# 601_GridPos6.net
KiCad netlist of a schematic drawn in Altium Designer
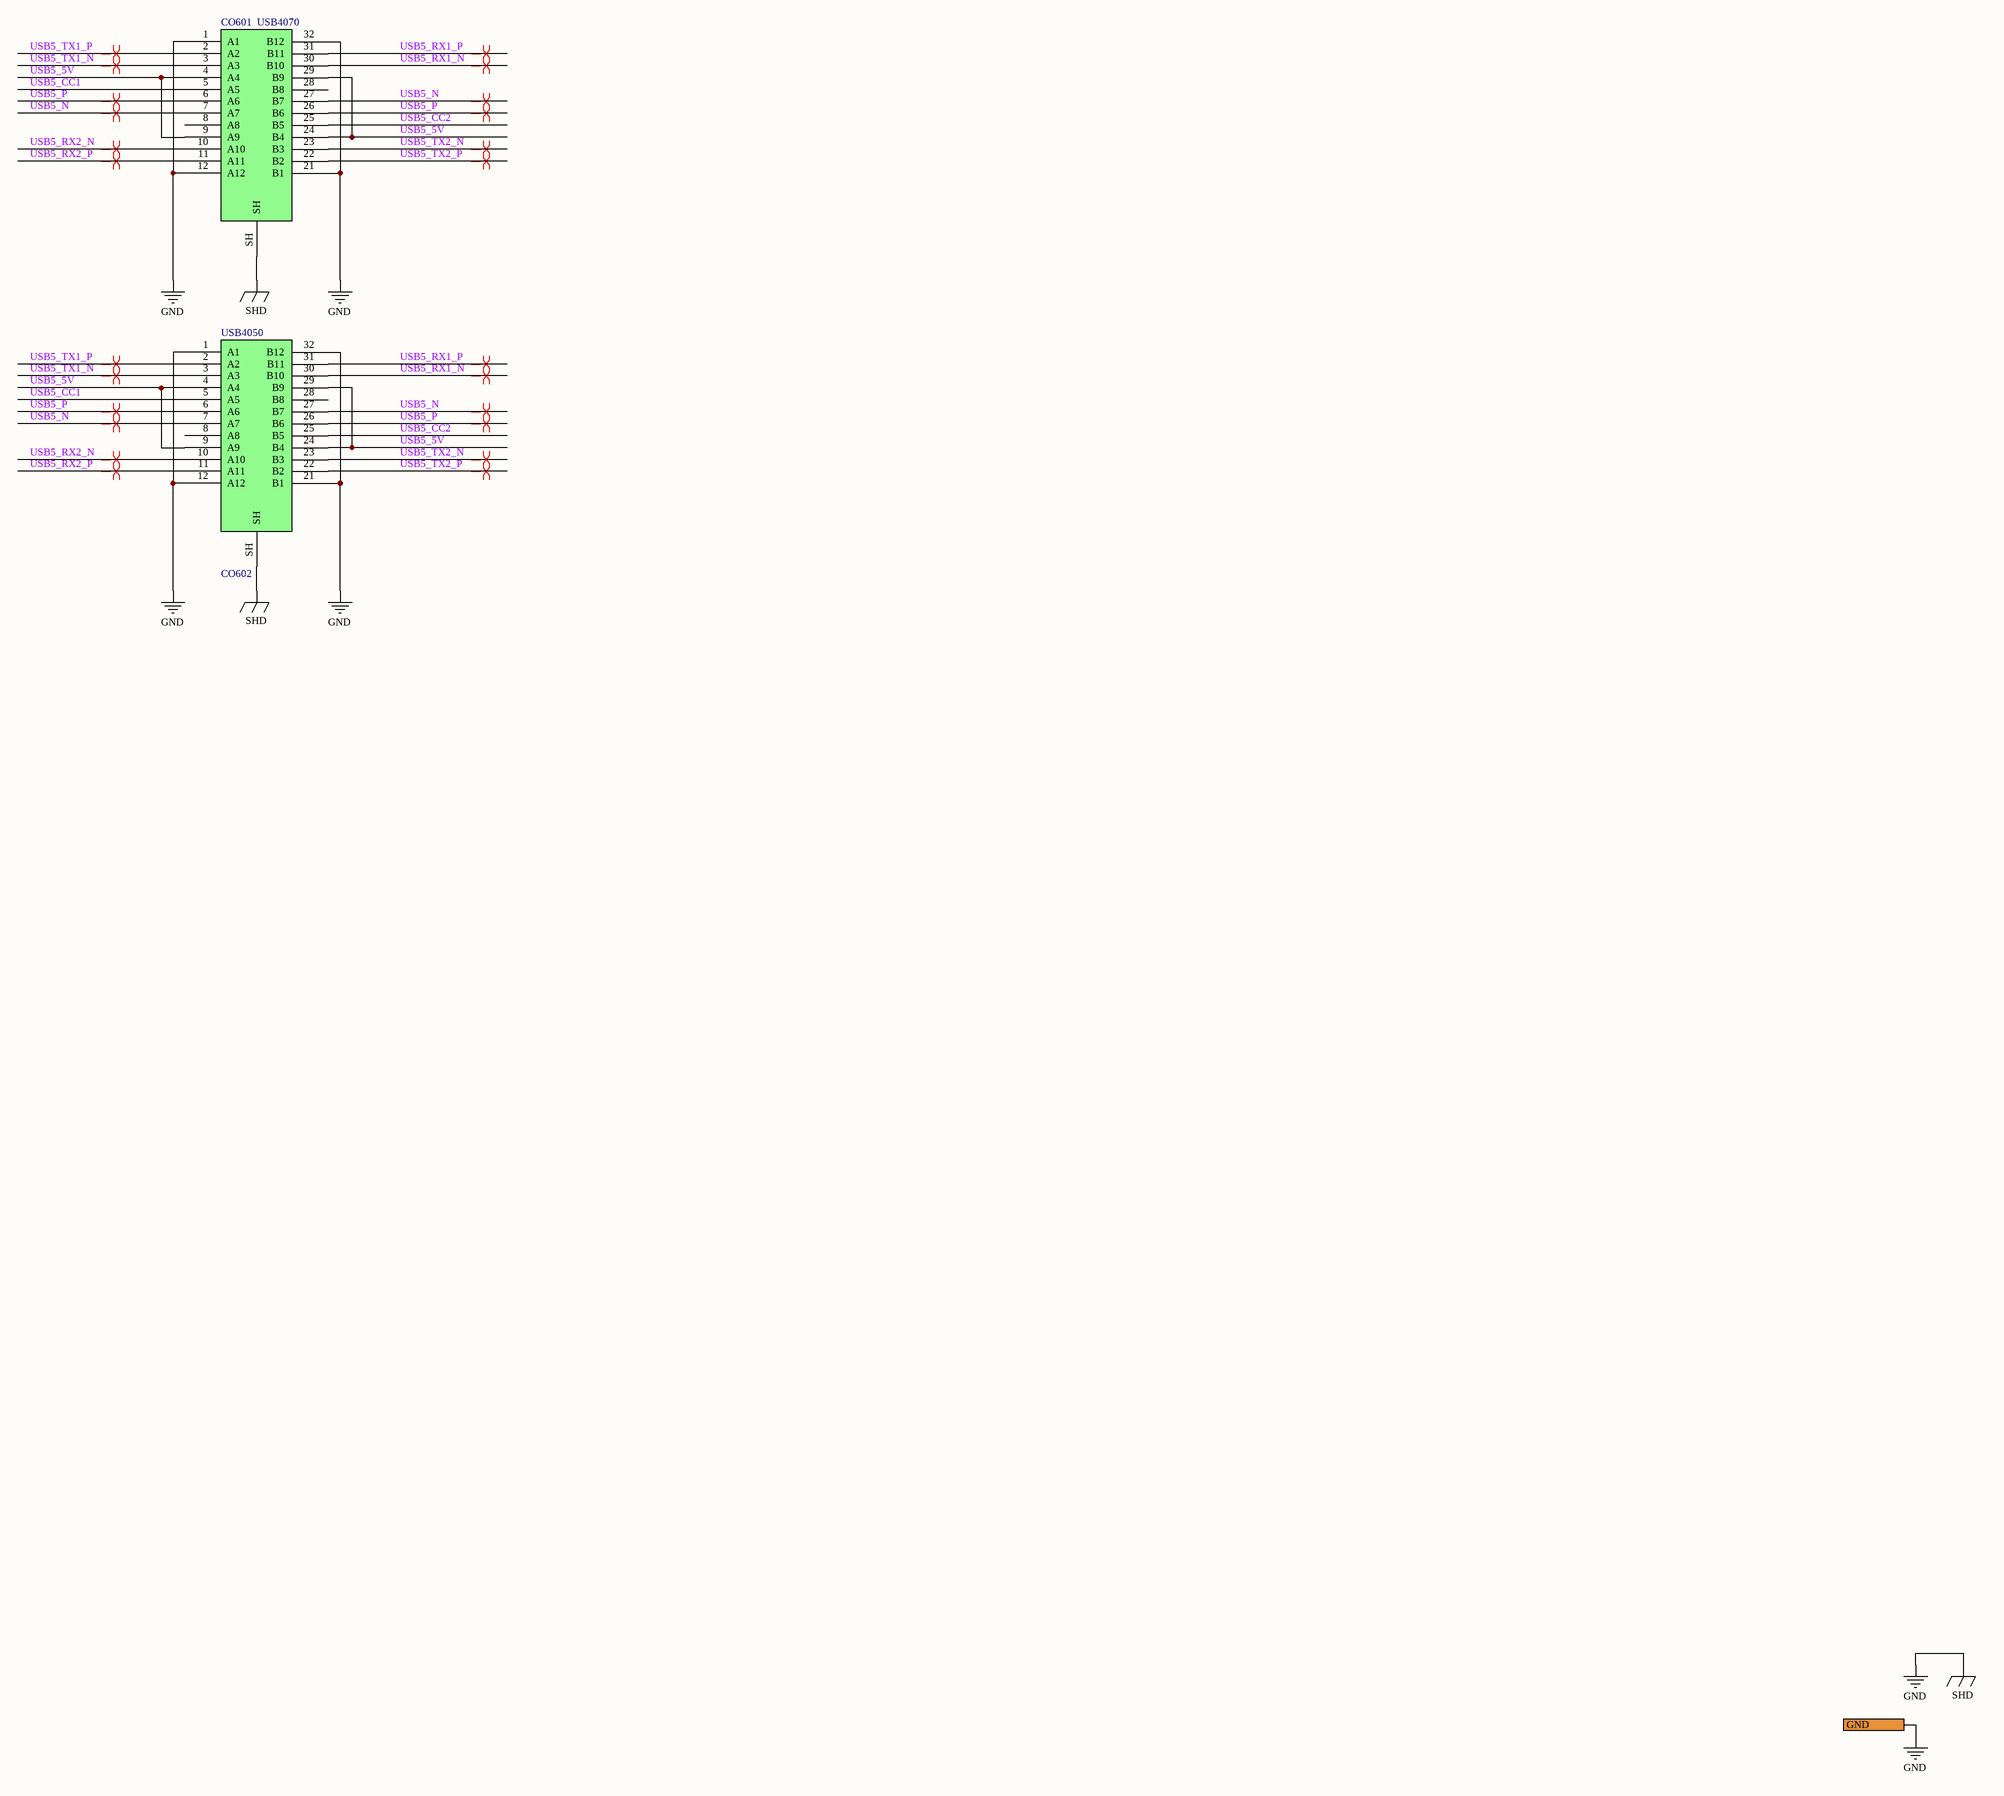
[diagram p0: 601_GridPos6.SchDoc]

(export (version "E")
  (design (tool "Eeschema 10.0.6"))
  (components
    (comp (ref "CO601")
      (value "USB4070")
      (footprint "USB4070-30-C")
      (description "USB4070-30-C")
      (fields (field (name "REFVAL") "USB4070") (field (name "PART NUMBER") "CO0021"))
      (libsource (lib "GTS_Database") (part "USB-CC"))
    )
    (comp (ref "CO602")
      (value "USB4050")
      (footprint "USB4050-30-A")
      (description "USB C connector Receptacle Horizontal")
      (fields
        (field (name "REFVAL") "USB4050")
        (field (name "PART NUMBER") "CO0039")
        (field (name "MANFACTPART") "USB4050-30-A")
      )
      (libsource (lib "") (part "USB-CC_1"))
    )
  )
  (nets
    (net (code "1") (name "/USB5_5V") (class "Default")
      (node (ref "CO601") (pin "24") (pinfunction "B4_24") (pintype "passive"))
      (node (ref "CO601") (pin "29") (pinfunction "B9_29") (pintype "passive"))
      (node (ref "CO601") (pin "4") (pinfunction "A4_4") (pintype "passive"))
      (node (ref "CO601") (pin "9") (pinfunction "A9_9") (pintype "passive"))
      (node (ref "CO602") (pin "24") (pinfunction "B4_24") (pintype "passive"))
      (node (ref "CO602") (pin "29") (pinfunction "B9_29") (pintype "passive"))
      (node (ref "CO602") (pin "4") (pinfunction "A4_4") (pintype "passive"))
      (node (ref "CO602") (pin "9") (pinfunction "A9_9") (pintype "passive"))
    )
    (net (code "2") (name "/USB5_CC1") (class "Default")
      (node (ref "CO601") (pin "5") (pinfunction "A5_5") (pintype "passive"))
      (node (ref "CO602") (pin "5") (pinfunction "A5_5") (pintype "passive"))
    )
    (net (code "3") (name "/USB5_CC2") (class "Default")
      (node (ref "CO601") (pin "25") (pinfunction "B5_25") (pintype "passive"))
      (node (ref "CO602") (pin "25") (pinfunction "B5_25") (pintype "passive"))
    )
    (net (code "4") (name "/USB5_N") (class "Default")
      (node (ref "CO601") (pin "27") (pinfunction "B7_27") (pintype "passive"))
      (node (ref "CO601") (pin "7") (pinfunction "A7_7") (pintype "passive"))
      (node (ref "CO602") (pin "27") (pinfunction "B7_27") (pintype "passive"))
      (node (ref "CO602") (pin "7") (pinfunction "A7_7") (pintype "passive"))
    )
    (net (code "5") (name "/USB5_P") (class "Default")
      (node (ref "CO601") (pin "26") (pinfunction "B6_26") (pintype "passive"))
      (node (ref "CO601") (pin "6") (pinfunction "A6_6") (pintype "passive"))
      (node (ref "CO602") (pin "26") (pinfunction "B6_26") (pintype "passive"))
      (node (ref "CO602") (pin "6") (pinfunction "A6_6") (pintype "passive"))
    )
    (net (code "6") (name "/USB5_RX1_N") (class "Default")
      (node (ref "CO601") (pin "30") (pinfunction "B10_30") (pintype "passive"))
      (node (ref "CO602") (pin "30") (pinfunction "B10_30") (pintype "passive"))
    )
    (net (code "7") (name "/USB5_RX1_P") (class "Default")
      (node (ref "CO601") (pin "31") (pinfunction "B11_31") (pintype "passive"))
      (node (ref "CO602") (pin "31") (pinfunction "B11_31") (pintype "passive"))
    )
    (net (code "8") (name "/USB5_RX2_N") (class "Default")
      (node (ref "CO601") (pin "10") (pinfunction "A10_10") (pintype "passive"))
      (node (ref "CO602") (pin "10") (pinfunction "A10_10") (pintype "passive"))
    )
    (net (code "9") (name "/USB5_RX2_P") (class "Default")
      (node (ref "CO601") (pin "11") (pinfunction "A11_11") (pintype "passive"))
      (node (ref "CO602") (pin "11") (pinfunction "A11_11") (pintype "passive"))
    )
    (net (code "10") (name "/USB5_TX1_N") (class "Default")
      (node (ref "CO601") (pin "3") (pinfunction "A3_3") (pintype "passive"))
      (node (ref "CO602") (pin "3") (pinfunction "A3_3") (pintype "passive"))
    )
    (net (code "11") (name "/USB5_TX1_P") (class "Default")
      (node (ref "CO601") (pin "2") (pinfunction "A2_2") (pintype "passive"))
      (node (ref "CO602") (pin "2") (pinfunction "A2_2") (pintype "passive"))
    )
    (net (code "12") (name "/USB5_TX2_N") (class "Default")
      (node (ref "CO601") (pin "23") (pinfunction "B3_23") (pintype "passive"))
      (node (ref "CO602") (pin "23") (pinfunction "B3_23") (pintype "passive"))
    )
    (net (code "13") (name "/USB5_TX2_P") (class "Default")
      (node (ref "CO601") (pin "22") (pinfunction "B2_22") (pintype "passive"))
      (node (ref "CO602") (pin "22") (pinfunction "B2_22") (pintype "passive"))
    )
    (net (code "14") (name "GND") (class "Default")
      (node (ref "CO601") (pin "1") (pinfunction "A1_1") (pintype "passive"))
      (node (ref "CO601") (pin "12") (pinfunction "A12_12") (pintype "passive"))
      (node (ref "CO601") (pin "21") (pinfunction "B1_21") (pintype "passive"))
      (node (ref "CO601") (pin "32") (pinfunction "B12_32") (pintype "passive"))
      (node (ref "CO601") (pin "SH") (pinfunction "SH_SH") (pintype "power_in"))
      (node (ref "CO602") (pin "1") (pinfunction "A1_1") (pintype "passive"))
      (node (ref "CO602") (pin "12") (pinfunction "A12_12") (pintype "passive"))
      (node (ref "CO602") (pin "21") (pinfunction "B1_21") (pintype "passive"))
      (node (ref "CO602") (pin "32") (pinfunction "B12_32") (pintype "passive"))
      (node (ref "CO602") (pin "SH") (pinfunction "SH_SH") (pintype "power_in"))
    )
    (net (code "15") (name "unconnected-(CO601-A8-Pad8)") (class "Default")
      (node (ref "CO601") (pin "8") (pinfunction "A8_8") (pintype "passive"))
    )
    (net (code "16") (name "unconnected-(CO601-B8-Pad28)") (class "Default")
      (node (ref "CO601") (pin "28") (pinfunction "B8_28") (pintype "passive"))
    )
    (net (code "17") (name "unconnected-(CO602-A8-Pad8)") (class "Default")
      (node (ref "CO602") (pin "8") (pinfunction "A8_8") (pintype "passive"))
    )
    (net (code "18") (name "unconnected-(CO602-B8-Pad28)") (class "Default")
      (node (ref "CO602") (pin "28") (pinfunction "B8_28") (pintype "passive"))
    )
  )
)
